# 51-2001-01-8_04_Power_Module_Schematic.net
KiCad netlist of a schematic drawn in Altium Designer
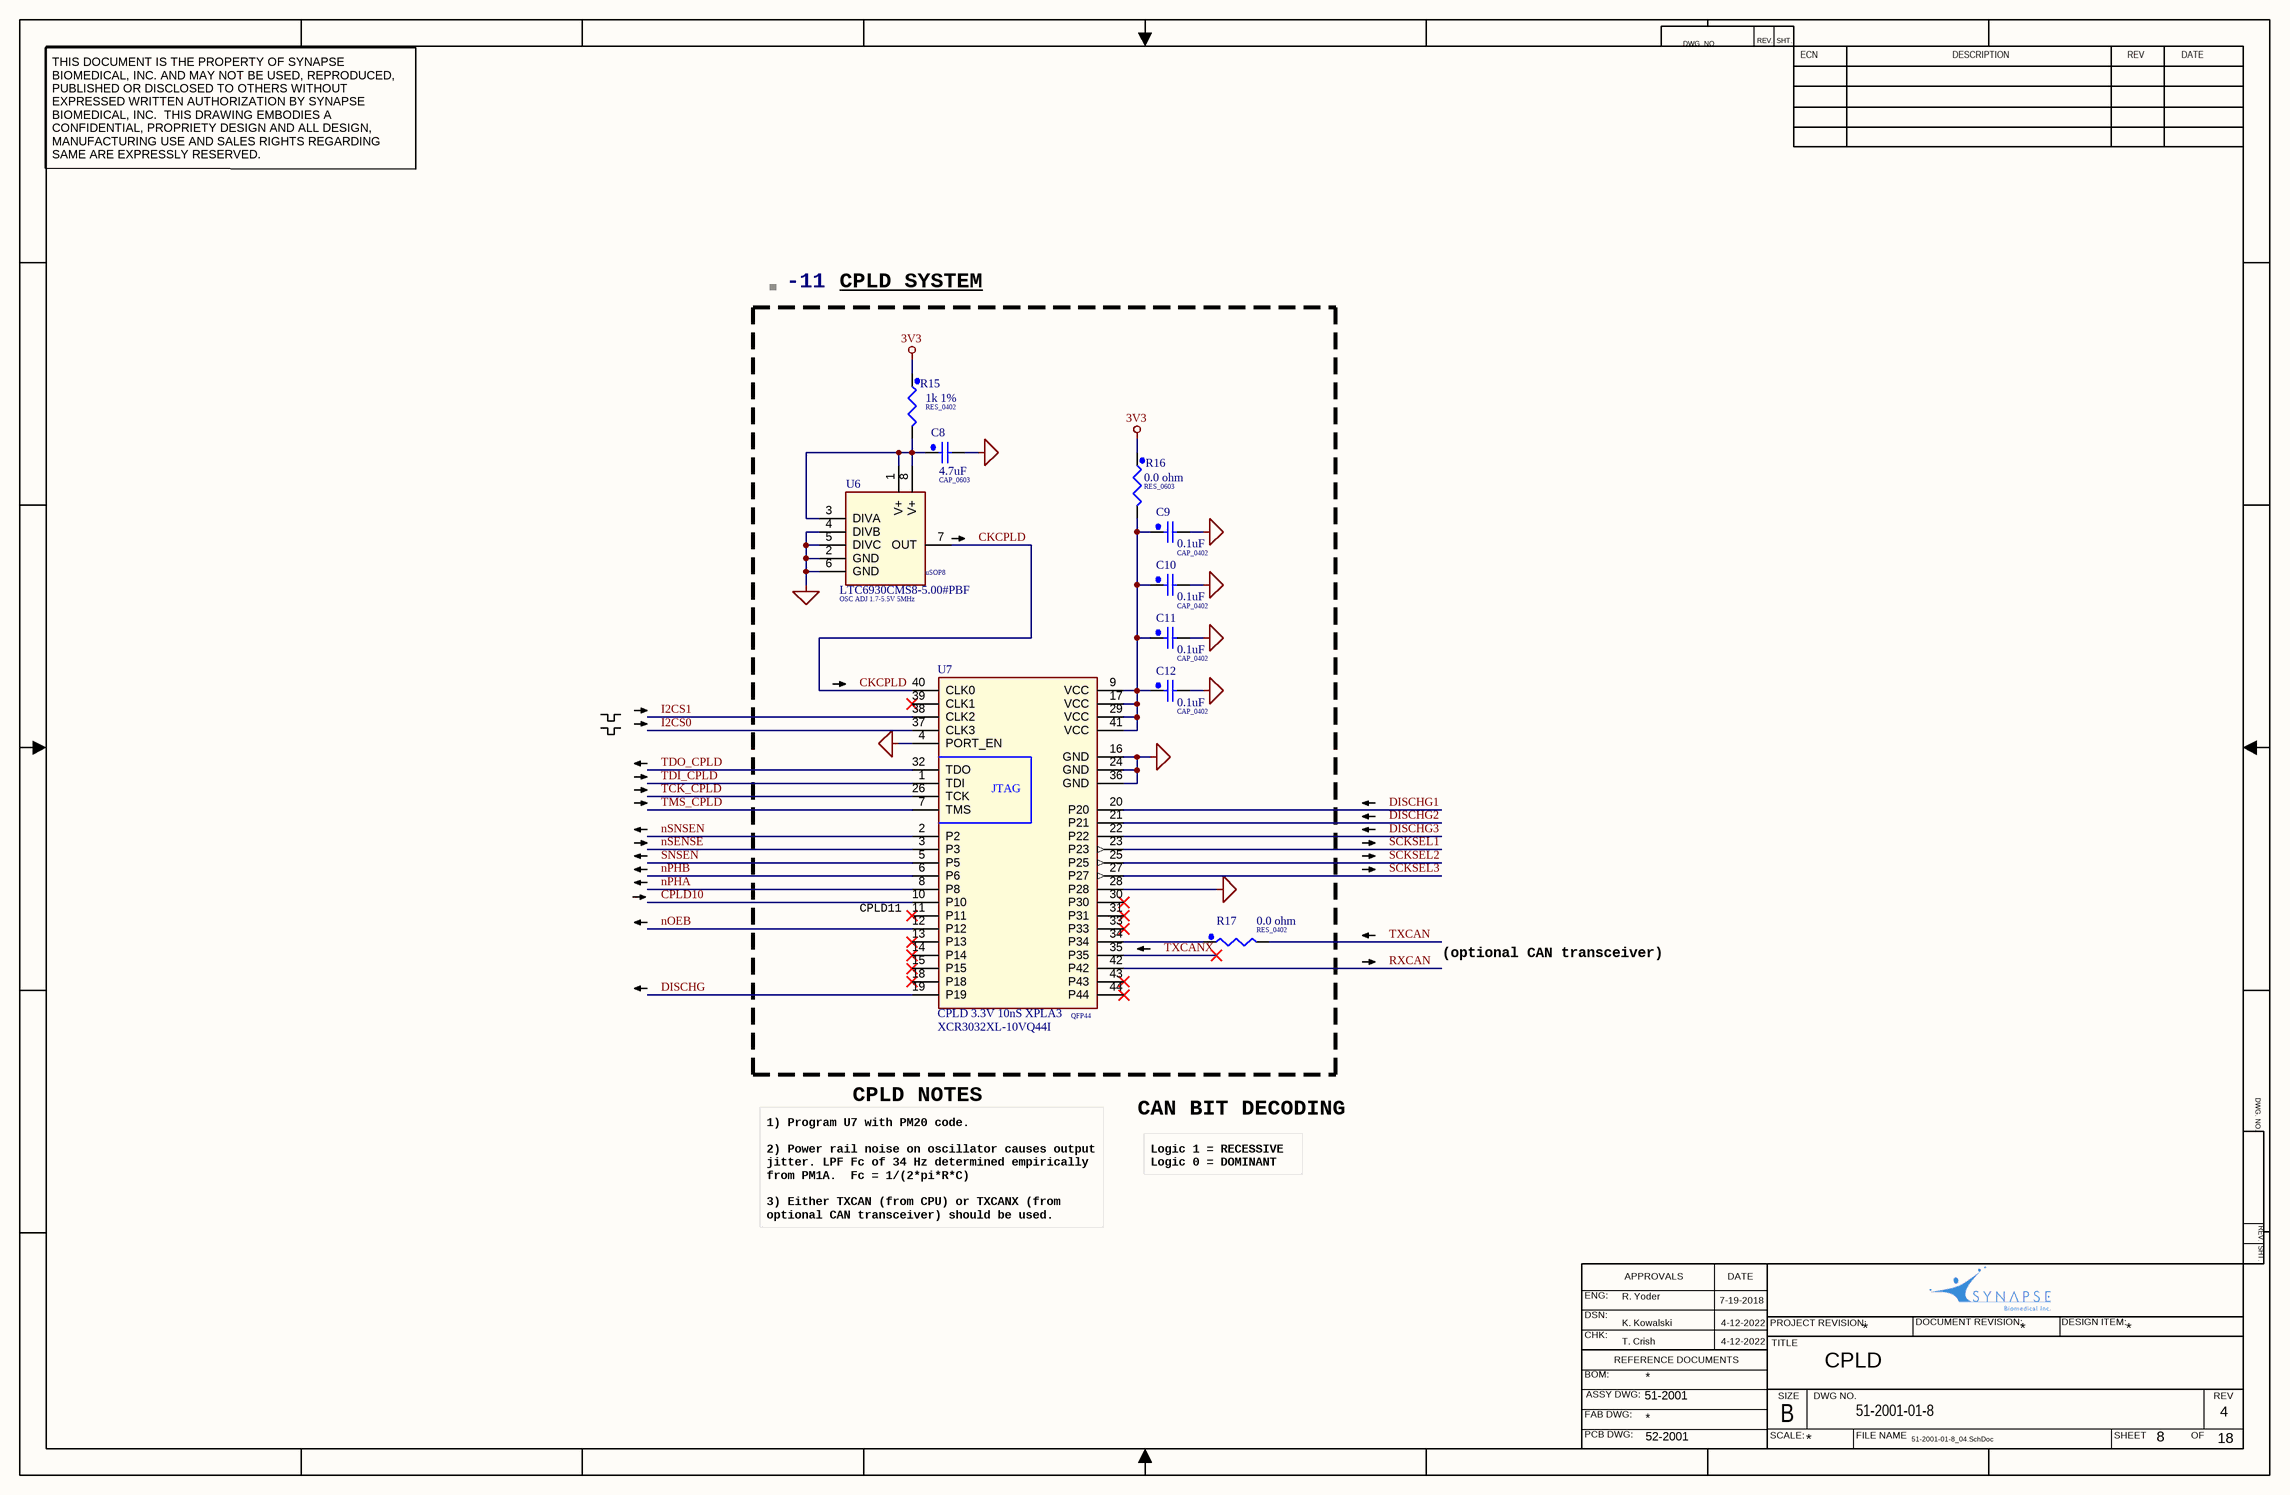
[diagram p0: 51-2001-01-8_04 Power Module Schematic.SchDoc]

(export (version "E")
  (design (tool "Eeschema 10.0.6"))
  (components
    (comp (ref "-11")
      (value "BOM_S1")
      (description "BOM item small graphic")
      (fields (field (name "XDESCRIPTION") "CPLD SYSTEM"))
      (libsource (lib "BOM_sym") (part "BOM_S1"))
    )
    (comp (ref "C8")
      (value "4.7uF")
      (footprint "CAP_0603")
      (description "4.7uF, 10V, X5R, 10%, 0603, RoHS")
      (fields
        (field (name "MFR") "Murata Electronics North America")
        (field (name "PACKAGEDESCRIPTION") "CAP_0603")
        (field (name "MPN") "GRM185R61A475KE11D")
      )
      (libsource (lib "NNPS Integrated Parts") (part "LMK107BJ475KA-T"))
    )
    (comp (ref "C9")
      (value "0.1uF")
      (footprint "CAP_0402")
      (description "0.1uF, 16V, X7R, 0402, RoHS")
      (fields
        (field (name "MFR") "Murata")
        (field (name "PACKAGEDESCRIPTION") "CAP_0402")
        (field (name "MPN") "GRM155R71C104KA88D")
      )
      (libsource (lib "NNPS Integrated Parts") (part "GRM155R71C104KA88D"))
    )
    (comp (ref "C10")
      (value "0.1uF")
      (footprint "CAP_0402")
      (description "0.1uF, 16V, X7R, 0402, RoHS")
      (fields
        (field (name "MFR") "Murata")
        (field (name "PACKAGEDESCRIPTION") "CAP_0402")
        (field (name "MPN") "GRM155R71C104KA88D")
      )
      (libsource (lib "NNPS Integrated Parts") (part "GRM155R71C104KA88D"))
    )
    (comp (ref "C11")
      (value "0.1uF")
      (footprint "CAP_0402")
      (description "0.1uF, 16V, X7R, 0402, RoHS")
      (fields
        (field (name "MFR") "Murata")
        (field (name "PACKAGEDESCRIPTION") "CAP_0402")
        (field (name "MPN") "GRM155R71C104KA88D")
      )
      (libsource (lib "NNPS Integrated Parts") (part "GRM155R71C104KA88D"))
    )
    (comp (ref "C12")
      (value "0.1uF")
      (footprint "CAP_0402")
      (description "0.1uF, 16V, X7R, 0402, RoHS")
      (fields
        (field (name "MFR") "Murata")
        (field (name "PACKAGEDESCRIPTION") "CAP_0402")
        (field (name "MPN") "GRM155R71C104KA88D")
      )
      (libsource (lib "NNPS Integrated Parts") (part "GRM155R71C104KA88D"))
    )
    (comp (ref "R15")
      (value "1k 1%")
      (footprint "RES_0402")
      (description "1.0k ohm 1% 1/16W smd 0402 RoHS")
      (fields
        (field (name "MFR") "Vishay Dale")
        (field (name "PACKAGEDESCRIPTION") "RES_0402")
        (field (name "MPN") "CRCW04021K00FKED")
      )
      (libsource (lib "NNPS Integrated Parts") (part "MCR01MZPF1001"))
    )
    (comp (ref "R16")
      (value "0.0 ohm")
      (footprint "RES_0603")
      (description "0.0 ohm, 1/16W, 0603, RoHS")
      (fields
        (field (name "MFR") "Vishay Dale")
        (field (name "PACKAGEDESCRIPTION") "RES_0603")
        (field (name "MPN") "CRCW06030000Z0EA")
      )
      (libsource (lib "NNPS Integrated Parts") (part "MCR03ERTJ000"))
    )
    (comp (ref "R17")
      (value "0.0 ohm")
      (footprint "RES_0402")
      (description "0.0 ohm, 1/16W, 0402, RoHS")
      (fields
        (field (name "MFR") "Vishay Dale")
        (field (name "PACKAGEDESCRIPTION") "RES_0402")
        (field (name "MPN") "CRCW04021K00FKED")
      )
      (libsource (lib "NNPS Integrated Parts") (part "MCR01MZPJ000"))
    )
    (comp (ref "U6")
      (value "OSC ADJ 1.7-5.5V 5MHz")
      (footprint "MSOP-8L")
      (description "Precision µPower Oscillator, ADJ 1.7-5.5V,5MHz, uSOP8, RoHS")
      (fields
        (field (name "PACKAGEDESCRIPTION") "uSOP8")
        (field (name "MFR") "Linear Technology")
        (field (name "MPN") "LTC6930CMS8-5.00#PBF")
      )
      (libsource (lib "NNPS Integrated Parts") (part "LTC6930CMS8-5.00#PBF"))
    )
    (comp (ref "U7")
      (value "CPLD 3.3V 10nS XPLA3")
      (footprint "VQFP-44")
      (description "CPLD, 3.3V, 10nS, XPLA3, QFP48, RoHS")
      (fields
        (field (name "MFR") "Xilinx")
        (field (name "PACKAGEDESCRIPTION") "QFP44")
        (field (name "MPN") "XCR3032XL-10VQ44I")
      )
      (libsource (lib "NNPS Integrated Parts") (part "XCR3032XL-10VQ44I"))
    )
  )
  (nets
    (net (code "1") (name "/CKCPLD") (class "Default")
      (node (ref "U6") (pin "7") (pinfunction "OUT_7") (pintype "passive"))
      (node (ref "U7") (pin "40") (pinfunction "CLK0_40") (pintype "passive"))
    )
    (net (code "2") (name "/CPLD10") (class "Default")
      (node (ref "U7") (pin "10") (pinfunction "P10_10") (pintype "passive"))
    )
    (net (code "3") (name "/DISCHG") (class "Default")
      (node (ref "U7") (pin "19") (pinfunction "P19_19") (pintype "passive"))
    )
    (net (code "4") (name "/DISCHG1") (class "Default")
      (node (ref "U7") (pin "20") (pinfunction "P20_20") (pintype "passive"))
    )
    (net (code "5") (name "/DISCHG2") (class "Default")
      (node (ref "U7") (pin "21") (pinfunction "P21_21") (pintype "passive"))
    )
    (net (code "6") (name "/DISCHG3") (class "Default")
      (node (ref "U7") (pin "22") (pinfunction "P22_22") (pintype "passive"))
    )
    (net (code "7") (name "/I2CS0") (class "Default")
      (node (ref "U7") (pin "37") (pinfunction "CLK3_37") (pintype "passive"))
    )
    (net (code "8") (name "/I2CS1") (class "Default")
      (node (ref "U7") (pin "38") (pinfunction "CLK2_38") (pintype "passive"))
    )
    (net (code "9") (name "/RXCAN") (class "Default")
      (node (ref "U7") (pin "42") (pinfunction "P42_42") (pintype "passive"))
    )
    (net (code "10") (name "/SCKSEL1") (class "Default")
      (node (ref "U7") (pin "23") (pinfunction "P23_23") (pintype "output"))
    )
    (net (code "11") (name "/SCKSEL2") (class "Default")
      (node (ref "U7") (pin "25") (pinfunction "P25_25") (pintype "output"))
    )
    (net (code "12") (name "/SCKSEL3") (class "Default")
      (node (ref "U7") (pin "27") (pinfunction "P27_27") (pintype "output"))
    )
    (net (code "13") (name "/SNSEN") (class "Default")
      (node (ref "U7") (pin "5") (pinfunction "P5_5") (pintype "passive"))
    )
    (net (code "14") (name "/TCK_CPLD") (class "Default")
      (node (ref "U7") (pin "26") (pinfunction "TCK_26") (pintype "passive"))
    )
    (net (code "15") (name "/TDI_CPLD") (class "Default")
      (node (ref "U7") (pin "1") (pinfunction "TDI_1") (pintype "passive"))
    )
    (net (code "16") (name "/TDO_CPLD") (class "Default")
      (node (ref "U7") (pin "32") (pinfunction "TDO_32") (pintype "passive"))
    )
    (net (code "17") (name "/TMS_CPLD") (class "Default")
      (node (ref "U7") (pin "7") (pinfunction "TMS_7") (pintype "passive"))
    )
    (net (code "18") (name "/TXCAN") (class "Default")
      (node (ref "R17") (pin "2") (pinfunction "2_2") (pintype "passive"))
    )
    (net (code "19") (name "/TXCANX") (class "Default")
      (node (ref "U7") (pin "35") (pinfunction "P35_35") (pintype "passive+no_connect"))
    )
    (net (code "20") (name "/nOEB") (class "Default")
      (node (ref "U7") (pin "12") (pinfunction "P12_12") (pintype "passive"))
    )
    (net (code "21") (name "/nPHA") (class "Default")
      (node (ref "U7") (pin "8") (pinfunction "P8_8") (pintype "passive"))
    )
    (net (code "22") (name "/nPHB") (class "Default")
      (node (ref "U7") (pin "6") (pinfunction "P6_6") (pintype "passive"))
    )
    (net (code "23") (name "/nSENSE") (class "Default")
      (node (ref "U7") (pin "3") (pinfunction "P3_3") (pintype "passive"))
    )
    (net (code "24") (name "/nSNSEN") (class "Default")
      (node (ref "U7") (pin "2") (pinfunction "P2_2") (pintype "passive"))
    )
    (net (code "25") (name "3V3") (class "Default")
      (node (ref "R15") (pin "1") (pinfunction "1_1") (pintype "passive"))
      (node (ref "R16") (pin "1") (pinfunction "1_1") (pintype "passive"))
    )
    (net (code "26") (name "GND") (class "Default")
      (node (ref "C10") (pin "2") (pinfunction "2_2") (pintype "passive"))
      (node (ref "C11") (pin "2") (pinfunction "2_2") (pintype "passive"))
      (node (ref "C12") (pin "2") (pinfunction "2_2") (pintype "passive"))
      (node (ref "C8") (pin "2") (pinfunction "2_2") (pintype "passive"))
      (node (ref "C9") (pin "2") (pinfunction "2_2") (pintype "passive"))
      (node (ref "U6") (pin "2") (pinfunction "GND_2") (pintype "passive"))
      (node (ref "U6") (pin "4") (pinfunction "DIVB_4") (pintype "passive"))
      (node (ref "U6") (pin "5") (pinfunction "DIVC_5") (pintype "passive"))
      (node (ref "U6") (pin "6") (pinfunction "GND_6") (pintype "passive"))
      (node (ref "U7") (pin "16") (pinfunction "GND_16") (pintype "passive"))
      (node (ref "U7") (pin "24") (pinfunction "GND_24") (pintype "passive"))
      (node (ref "U7") (pin "28") (pinfunction "P28_28") (pintype "passive"))
      (node (ref "U7") (pin "36") (pinfunction "GND_36") (pintype "passive"))
      (node (ref "U7") (pin "4") (pinfunction "PORT_EN_4") (pintype "passive"))
    )
    (net (code "27") (name "Net-(C10-Pad1)") (class "Default")
      (node (ref "C10") (pin "1") (pinfunction "1_1") (pintype "passive"))
      (node (ref "C11") (pin "1") (pinfunction "1_1") (pintype "passive"))
      (node (ref "C12") (pin "1") (pinfunction "1_1") (pintype "passive"))
      (node (ref "C9") (pin "1") (pinfunction "1_1") (pintype "passive"))
      (node (ref "R16") (pin "2") (pinfunction "2_2") (pintype "passive"))
      (node (ref "U7") (pin "17") (pinfunction "VCC_17") (pintype "passive"))
      (node (ref "U7") (pin "29") (pinfunction "VCC_29") (pintype "passive"))
      (node (ref "U7") (pin "41") (pinfunction "VCC_41") (pintype "passive"))
      (node (ref "U7") (pin "9") (pinfunction "VCC_9") (pintype "passive"))
    )
    (net (code "28") (name "Net-(U6-DIVA)") (class "Default")
      (node (ref "C8") (pin "1") (pinfunction "1_1") (pintype "passive"))
      (node (ref "R15") (pin "2") (pinfunction "2_2") (pintype "passive"))
      (node (ref "U6") (pin "1") (pinfunction "V+_1") (pintype "passive"))
      (node (ref "U6") (pin "3") (pinfunction "DIVA_3") (pintype "passive"))
      (node (ref "U6") (pin "8") (pinfunction "V+_8") (pintype "passive"))
    )
    (net (code "29") (name "Net-(U7-P34)") (class "Default")
      (node (ref "R17") (pin "1") (pinfunction "1_1") (pintype "passive"))
      (node (ref "U7") (pin "34") (pinfunction "P34_34") (pintype "passive"))
    )
    (net (code "30") (name "unconnected-(U7-CLK1-Pad39)") (class "Default")
      (node (ref "U7") (pin "39") (pinfunction "CLK1_39") (pintype "passive+no_connect"))
    )
    (net (code "31") (name "unconnected-(U7-P11-Pad11)") (class "Default")
      (node (ref "U7") (pin "11") (pinfunction "P11_11") (pintype "passive+no_connect"))
    )
    (net (code "32") (name "unconnected-(U7-P13-Pad13)") (class "Default")
      (node (ref "U7") (pin "13") (pinfunction "P13_13") (pintype "passive+no_connect"))
    )
    (net (code "33") (name "unconnected-(U7-P14-Pad14)") (class "Default")
      (node (ref "U7") (pin "14") (pinfunction "P14_14") (pintype "passive+no_connect"))
    )
    (net (code "34") (name "unconnected-(U7-P15-Pad15)") (class "Default")
      (node (ref "U7") (pin "15") (pinfunction "P15_15") (pintype "passive+no_connect"))
    )
    (net (code "35") (name "unconnected-(U7-P18-Pad18)") (class "Default")
      (node (ref "U7") (pin "18") (pinfunction "P18_18") (pintype "passive+no_connect"))
    )
    (net (code "36") (name "unconnected-(U7-P30-Pad30)") (class "Default")
      (node (ref "U7") (pin "30") (pinfunction "P30_30") (pintype "passive+no_connect"))
    )
    (net (code "37") (name "unconnected-(U7-P31-Pad31)") (class "Default")
      (node (ref "U7") (pin "31") (pinfunction "P31_31") (pintype "passive+no_connect"))
    )
    (net (code "38") (name "unconnected-(U7-P33-Pad33)") (class "Default")
      (node (ref "U7") (pin "33") (pinfunction "P33_33") (pintype "passive+no_connect"))
    )
    (net (code "39") (name "unconnected-(U7-P43-Pad43)") (class "Default")
      (node (ref "U7") (pin "43") (pinfunction "P43_43") (pintype "passive+no_connect"))
    )
    (net (code "40") (name "unconnected-(U7-P44-Pad44)") (class "Default")
      (node (ref "U7") (pin "44") (pinfunction "P44_44") (pintype "passive+no_connect"))
    )
  )
)
